# Charge_controller_CAR.net
KiCad netlist of a schematic drawn in EAGLE
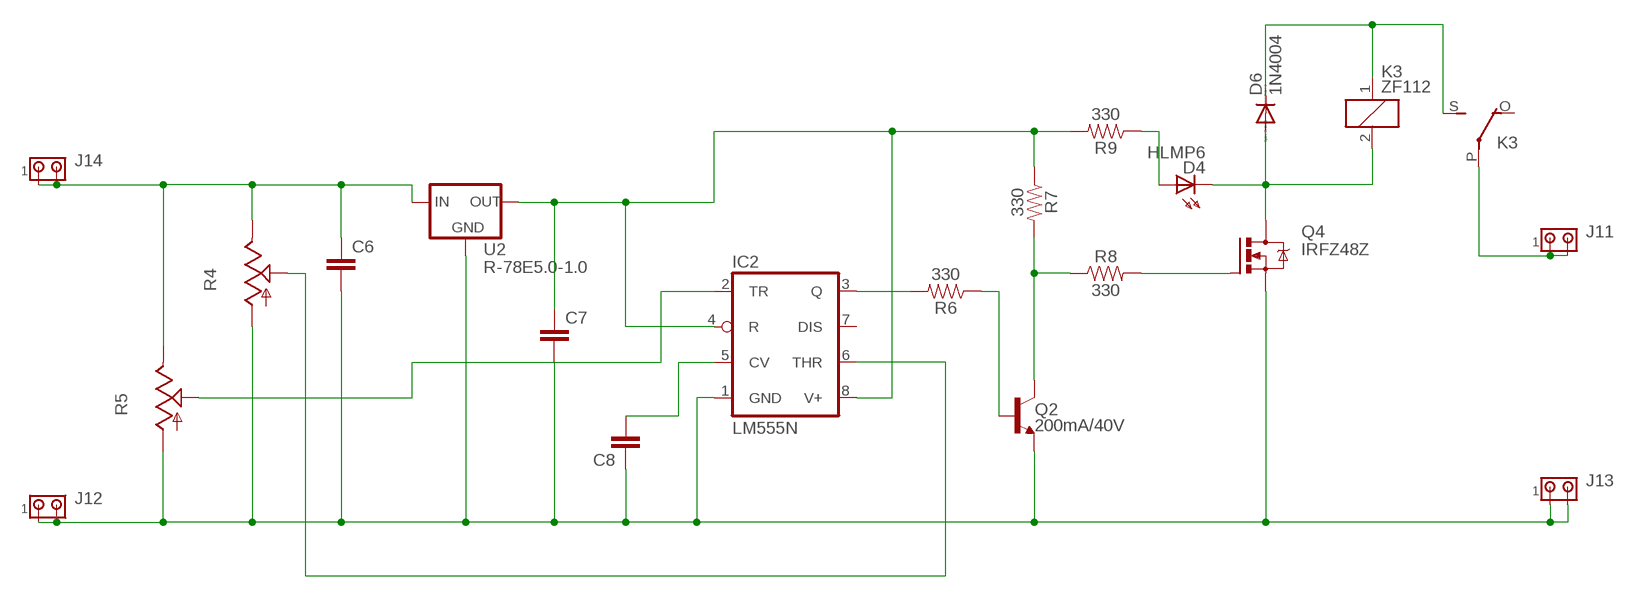
[diagram p0: schematic, sheet 1]

(export (version "E")
  (design (tool "Eeschema 10.0.6"))
  (components
    (comp (ref "C6")
      (value "C5/2.5")
      (footprint "eagle-import:C5B2.5")
      (libsource (lib "eagle-import") (part "C5/2.5"))
    )
    (comp (ref "C7")
      (value "C5/2.5")
      (footprint "eagle-import:C5B2.5")
      (libsource (lib "eagle-import") (part "C5/2.5"))
    )
    (comp (ref "C8")
      (value "C5/2.5")
      (footprint "eagle-import:C5B2.5")
      (libsource (lib "eagle-import") (part "C5/2.5"))
    )
    (comp (ref "D4")
      (value "HLMP6")
      (footprint "eagle-import:HLMP6")
      (fields (field (name "MF") "AGILENT TECHNOLOGIES") (field (name "MPN") "HLMP-6500"))
      (libsource (lib "eagle-import") (part "HLMP6"))
    )
    (comp (ref "D6")
      (value "1N4004")
      (footprint "eagle-import:DO41-10")
      (libsource (lib "eagle-import") (part "1N4004"))
    )
    (comp (ref "IC2")
      (value "LM555N")
      (footprint "eagle-import:DIL08")
      (libsource (lib "eagle-import") (part "555NLM"))
    )
    (comp (ref "J11")
      (value "MTA02-156")
      (footprint "eagle-import:1X2MTA")
      (libsource (lib "eagle-import") (part "MTA02-156"))
    )
    (comp (ref "J12")
      (value "MTA02-156")
      (footprint "eagle-import:1X2MTA")
      (libsource (lib "eagle-import") (part "MTA02-156"))
    )
    (comp (ref "J13")
      (value "MTA02-156")
      (footprint "eagle-import:1X2MTA")
      (libsource (lib "eagle-import") (part "MTA02-156"))
    )
    (comp (ref "J14")
      (value "MTA02-156")
      (footprint "eagle-import:1X2MTA")
      (libsource (lib "eagle-import") (part "MTA02-156"))
    )
    (comp (ref "K3")
      (value "ZF112")
      (footprint "eagle-import:ZF112")
      (libsource (lib "eagle-import") (part "ZF112"))
    )
    (comp (ref "Q2")
      (value "200mA/40V")
      (footprint "eagle-import:TO-92")
      (libsource (lib "eagle-import") (part "TRANS_NPN-2N3904"))
    )
    (comp (ref "Q4")
      (value "IRFZ48Z")
      (footprint "eagle-import:TO220BH")
      (libsource (lib "eagle-import") (part "IRFZ48Z"))
    )
    (comp (ref "R4")
      (value "TRIM_US-CA6V")
      (footprint "eagle-import:CA6V")
      (libsource (lib "eagle-import") (part "TRIM_US-CA6V"))
    )
    (comp (ref "R5")
      (value "TRIM_US-CA6V")
      (footprint "eagle-import:CA6V")
      (libsource (lib "eagle-import") (part "TRIM_US-CA6V"))
    )
    (comp (ref "R6")
      (value "330")
      (footprint "eagle-import:AXIAL-0.3")
      (libsource (lib "eagle-import") (part "330OHM-HORIZ-1/10W-5%"))
    )
    (comp (ref "R7")
      (value "330")
      (footprint "eagle-import:AXIAL-0.3")
      (libsource (lib "eagle-import") (part "330OHM-HORIZ-1/10W-5%"))
    )
    (comp (ref "R8")
      (value "330")
      (footprint "eagle-import:AXIAL-0.3")
      (libsource (lib "eagle-import") (part "330OHM-HORIZ-1/10W-5%"))
    )
    (comp (ref "R9")
      (value "330")
      (footprint "eagle-import:AXIAL-0.3")
      (libsource (lib "eagle-import") (part "330OHM-HORIZ-1/10W-5%"))
    )
    (comp (ref "U2")
      (value "R-78E5.0-1.0")
      (footprint "eagle-import:DC-DC_CONVERTER_78XX")
      (libsource (lib "eagle-import") (part "R-78E5.0-1.0"))
    )
  )
  (nets
    (net (code "1") (name "Net-(D4-PadK)") (class "Default")
      (node (ref "D4") (pin "K") (pinfunction "K_K") (pintype "passive"))
      (node (ref "D6") (pin "A") (pinfunction "A_A") (pintype "passive"))
      (node (ref "K3") (pin "2") (pinfunction "2_2") (pintype "passive"))
      (node (ref "Q4") (pin "D") (pinfunction "D_D") (pintype "passive"))
    )
    (net (code "2") (name "Net-(D6-PadC)") (class "Default")
      (node (ref "D6") (pin "C") (pinfunction "C_C") (pintype "passive"))
      (node (ref "K3") (pin "1") (pinfunction "1_1") (pintype "passive"))
      (node (ref "K3") (pin "S") (pinfunction "S_S") (pintype "passive"))
    )
    (net (code "3") (name "Net-(IC2-CV)") (class "Default")
      (node (ref "C8") (pin "2") (pinfunction "2_2") (pintype "passive"))
      (node (ref "IC2") (pin "5") (pinfunction "CV_5") (pintype "input"))
    )
    (net (code "4") (name "Net-(IC2-GND)") (class "Default")
      (node (ref "C6") (pin "2") (pinfunction "2_2") (pintype "passive"))
      (node (ref "C7") (pin "2") (pinfunction "2_2") (pintype "passive"))
      (node (ref "C8") (pin "1") (pinfunction "1_1") (pintype "passive"))
      (node (ref "IC2") (pin "1") (pinfunction "GND_1") (pintype "power_in"))
      (node (ref "J12") (pin "1") (pinfunction "1_1") (pintype "passive"))
      (node (ref "J12") (pin "2") (pinfunction "2_2") (pintype "passive"))
      (node (ref "J13") (pin "1") (pinfunction "1_1") (pintype "passive"))
      (node (ref "J13") (pin "2") (pinfunction "2_2") (pintype "passive"))
      (node (ref "Q2") (pin "1") (pinfunction "E_1") (pintype "passive"))
      (node (ref "Q4") (pin "S") (pinfunction "S_S") (pintype "passive"))
      (node (ref "R4") (pin "A") (pinfunction "A_A") (pintype "passive"))
      (node (ref "R5") (pin "A") (pinfunction "A_A") (pintype "passive"))
      (node (ref "U2") (pin "GND") (pinfunction "GND_GND") (pintype "input"))
    )
    (net (code "5") (name "Net-(IC2-Q)") (class "Default")
      (node (ref "IC2") (pin "3") (pinfunction "Q_3") (pintype "output"))
      (node (ref "R6") (pin "P$2") (pinfunction "2_P$2") (pintype "passive"))
    )
    (net (code "6") (name "Net-(IC2-R)") (class "Default")
      (node (ref "C7") (pin "1") (pinfunction "1_1") (pintype "passive"))
      (node (ref "IC2") (pin "4") (pinfunction "R_4") (pintype "input"))
      (node (ref "IC2") (pin "8") (pinfunction "V+_8") (pintype "power_in"))
      (node (ref "R7") (pin "P$1") (pinfunction "1_P$1") (pintype "passive"))
      (node (ref "R9") (pin "P$2") (pinfunction "2_P$2") (pintype "passive"))
      (node (ref "U2") (pin "VOUT") (pinfunction "OUT_VOUT") (pintype "passive"))
    )
    (net (code "7") (name "Net-(IC2-THR)") (class "Default")
      (node (ref "IC2") (pin "6") (pinfunction "THR_6") (pintype "input"))
      (node (ref "R4") (pin "S") (pinfunction "S_S") (pintype "passive"))
    )
    (net (code "8") (name "Net-(IC2-TR)") (class "Default")
      (node (ref "IC2") (pin "2") (pinfunction "TR_2") (pintype "input"))
      (node (ref "R5") (pin "S") (pinfunction "S_S") (pintype "passive"))
    )
    (net (code "9") (name "Net-(J11-Pad1)") (class "Default")
      (node (ref "J11") (pin "1") (pinfunction "1_1") (pintype "passive"))
      (node (ref "J11") (pin "2") (pinfunction "2_2") (pintype "passive"))
      (node (ref "K3") (pin "P") (pinfunction "P_P") (pintype "passive"))
    )
    (net (code "10") (name "Net-(Q2-B)") (class "Default")
      (node (ref "Q2") (pin "2") (pinfunction "B_2") (pintype "passive"))
      (node (ref "R6") (pin "P$1") (pinfunction "1_P$1") (pintype "passive"))
    )
    (net (code "11") (name "Net-(Q2-C)") (class "Default")
      (node (ref "Q2") (pin "3") (pinfunction "C_3") (pintype "passive"))
      (node (ref "R7") (pin "P$2") (pinfunction "2_P$2") (pintype "passive"))
      (node (ref "R8") (pin "P$1") (pinfunction "1_P$1") (pintype "passive"))
    )
    (net (code "12") (name "Net-(R8-2)") (class "Default")
      (node (ref "Q4") (pin "G") (pinfunction "G_G") (pintype "passive"))
      (node (ref "R8") (pin "P$2") (pinfunction "2_P$2") (pintype "passive"))
    )
    (net (code "13") (name "Net-(R9-1)") (class "Default")
      (node (ref "D4") (pin "A") (pinfunction "A_A") (pintype "passive"))
      (node (ref "R9") (pin "P$1") (pinfunction "1_P$1") (pintype "passive"))
    )
    (net (code "14") (name "Net-(U2-IN)") (class "Default")
      (node (ref "C6") (pin "1") (pinfunction "1_1") (pintype "passive"))
      (node (ref "J14") (pin "1") (pinfunction "1_1") (pintype "passive"))
      (node (ref "J14") (pin "2") (pinfunction "2_2") (pintype "passive"))
      (node (ref "R4") (pin "E") (pinfunction "E_E") (pintype "passive"))
      (node (ref "R5") (pin "E") (pinfunction "E_E") (pintype "passive"))
      (node (ref "U2") (pin "VIN") (pinfunction "IN_VIN") (pintype "input"))
    )
    (net (code "15") (name "unconnected-(IC2-DIS-Pad7)") (class "Default")
      (node (ref "IC2") (pin "7") (pinfunction "DIS_7") (pintype "input"))
    )
    (net (code "16") (name "unconnected-(K3-PadO)") (class "Default")
      (node (ref "K3") (pin "O") (pinfunction "O_O") (pintype "passive"))
    )
  )
)
